# usbcan_20190426.net
KiCad netlist of a schematic drawn in EAGLE
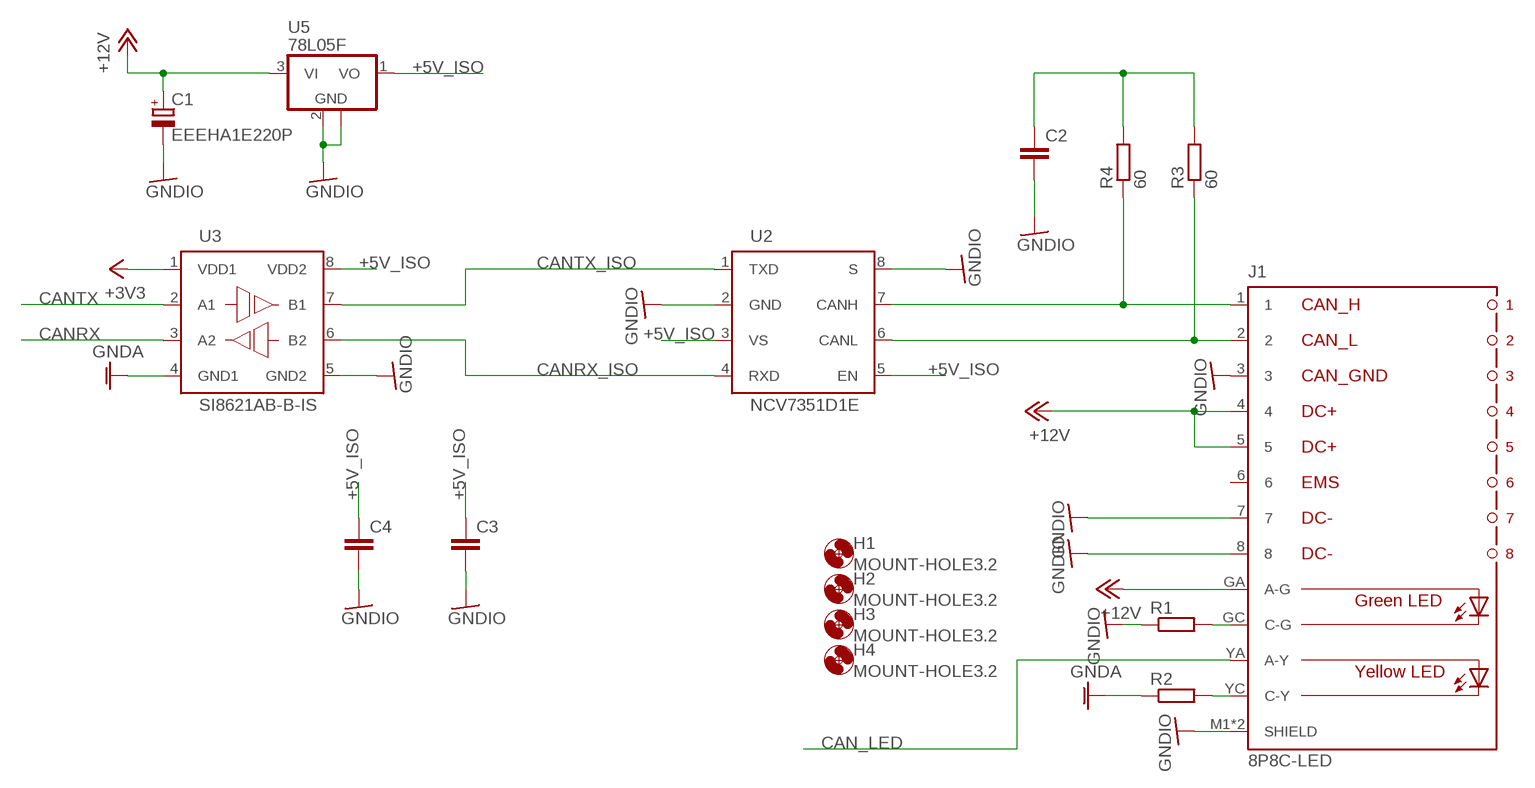
[diagram p0: schematic, sheet 1]
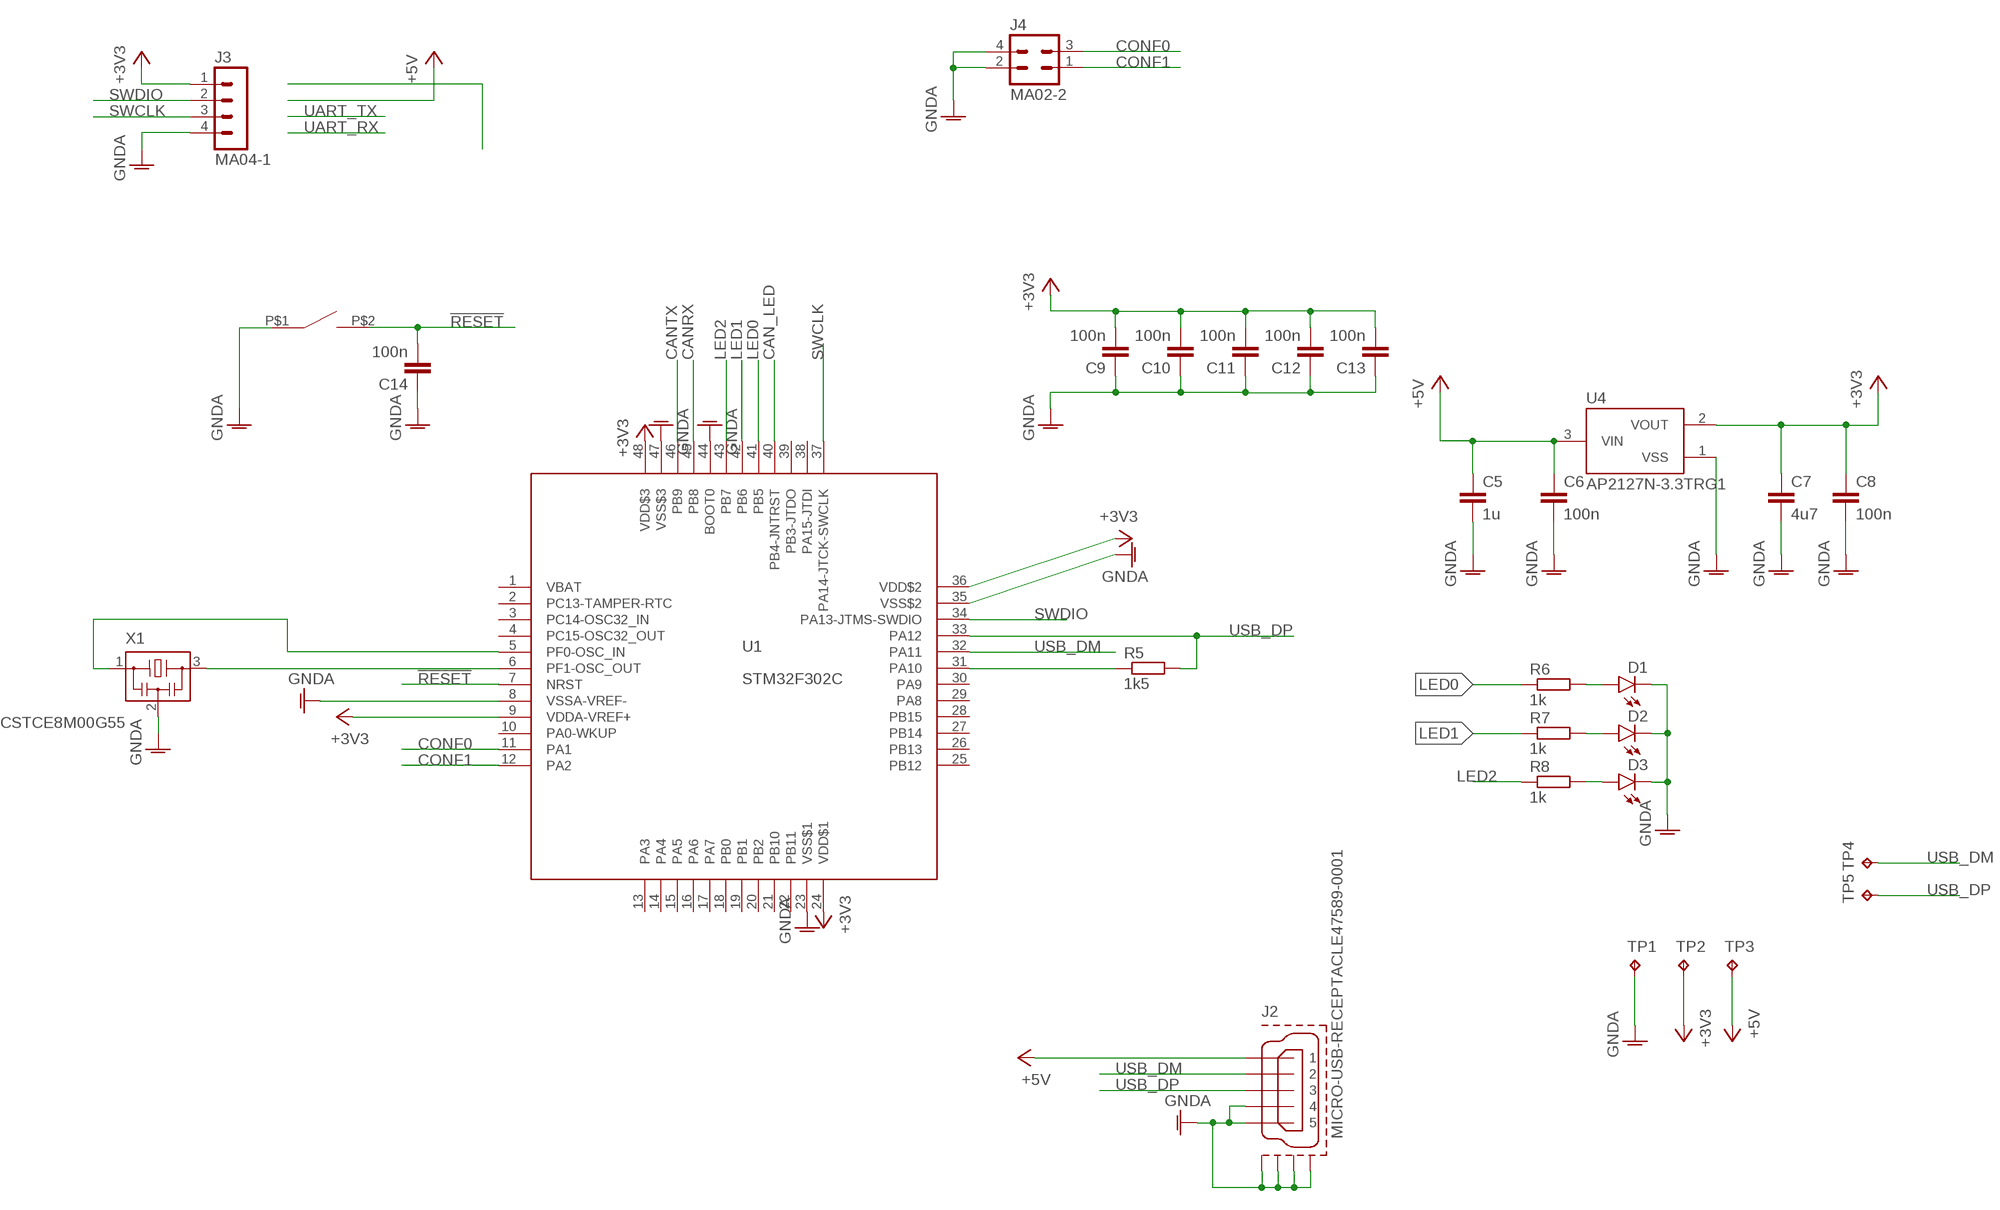
[diagram p1: schematic, sheet 2]

(export (version "E")
  (design (tool "Eeschema 10.0.6"))
  (components
    (comp (ref "C5")
      (value "1u")
      (footprint "eagle-import:C0603")
      (libsource (lib "eagle-import") (part "C-EUC0603"))
    )
    (comp (ref "C6")
      (value "100n")
      (footprint "eagle-import:C0603")
      (libsource (lib "eagle-import") (part "C-EUC0603"))
    )
    (comp (ref "C7")
      (value "4u7")
      (footprint "eagle-import:C0805")
      (libsource (lib "eagle-import") (part "C-EUC0805"))
    )
    (comp (ref "C8")
      (value "100n")
      (footprint "eagle-import:C0603")
      (libsource (lib "eagle-import") (part "C-EUC0603"))
    )
    (comp (ref "C9")
      (value "100n")
      (footprint "eagle-import:C0603")
      (libsource (lib "eagle-import") (part "C-EUC0603"))
    )
    (comp (ref "C10")
      (value "100n")
      (footprint "eagle-import:C0603")
      (libsource (lib "eagle-import") (part "C-EUC0603"))
    )
    (comp (ref "C11")
      (value "100n")
      (footprint "eagle-import:C0603")
      (libsource (lib "eagle-import") (part "C-EUC0603"))
    )
    (comp (ref "C12")
      (value "100n")
      (footprint "eagle-import:C0603")
      (libsource (lib "eagle-import") (part "C-EUC0603"))
    )
    (comp (ref "C13")
      (value "100n")
      (footprint "eagle-import:C0603")
      (libsource (lib "eagle-import") (part "C-EUC0603"))
    )
    (comp (ref "C14")
      (value "100n")
      (footprint "eagle-import:C0603")
      (libsource (lib "eagle-import") (part "C-EUC0603"))
    )
    (comp (ref "D1")
      (value "LEDCHIPLED_0805")
      (footprint "eagle-import:CHIPLED_0805")
      (libsource (lib "eagle-import") (part "LEDCHIPLED_0805"))
    )
    (comp (ref "D2")
      (value "LEDCHIPLED_0805")
      (footprint "eagle-import:CHIPLED_0805")
      (libsource (lib "eagle-import") (part "LEDCHIPLED_0805"))
    )
    (comp (ref "D3")
      (value "LEDCHIPLED_0805")
      (footprint "eagle-import:CHIPLED_0805")
      (libsource (lib "eagle-import") (part "LEDCHIPLED_0805"))
    )
    (comp (ref "J2")
      (value "MICRO-USB-RECEPTACLE47589-0001")
      (footprint "eagle-import:47589-0001")
      (libsource (lib "eagle-import") (part "MICRO-USB-RECEPTACLE47589-0001"))
    )
    (comp (ref "J3")
      (value "MA04-1")
      (footprint "eagle-import:MA04-1")
      (libsource (lib "eagle-import") (part "MA04-1"))
    )
    (comp (ref "J4")
      (value "MA02-2")
      (footprint "eagle-import:MA02-2W")
      (libsource (lib "eagle-import") (part "MA02-2"))
    )
    (comp (ref "R5")
      (value "1k5")
      (footprint "eagle-import:R0603")
      (libsource (lib "eagle-import") (part "R-EU_R0603"))
    )
    (comp (ref "R6")
      (value "1k")
      (footprint "eagle-import:R0603")
      (libsource (lib "eagle-import") (part "R-EU_R0603"))
    )
    (comp (ref "R7")
      (value "1k")
      (footprint "eagle-import:R0603")
      (libsource (lib "eagle-import") (part "R-EU_R0603"))
    )
    (comp (ref "R8")
      (value "1k")
      (footprint "eagle-import:R0603")
      (libsource (lib "eagle-import") (part "R-EU_R0603"))
    )
    (comp (ref "S1")
      (value "SWITCH_TACTILETOP")
      (footprint "eagle-import:SWITCH_TACTILE_3X6")
      (libsource (lib "eagle-import") (part "SWITCH_TACTILETOP"))
    )
    (comp (ref "TP1")
      (value "TPB1,27")
      (footprint "eagle-import:B1,27")
      (libsource (lib "eagle-import") (part "TPB1,27"))
    )
    (comp (ref "TP2")
      (value "TPB1,27")
      (footprint "eagle-import:B1,27")
      (libsource (lib "eagle-import") (part "TPB1,27"))
    )
    (comp (ref "TP3")
      (value "TPB1,27")
      (footprint "eagle-import:B1,27")
      (libsource (lib "eagle-import") (part "TPB1,27"))
    )
    (comp (ref "TP4")
      (value "TPB1,27")
      (footprint "eagle-import:B1,27")
      (libsource (lib "eagle-import") (part "TPB1,27"))
    )
    (comp (ref "TP5")
      (value "TPB1,27")
      (footprint "eagle-import:B1,27")
      (libsource (lib "eagle-import") (part "TPB1,27"))
    )
    (comp (ref "U1")
      (value "STM32F302C")
      (footprint "eagle-import:LQFP48")
      (libsource (lib "eagle-import") (part "STM32F303C"))
    )
    (comp (ref "U4")
      (value "AP2127N-3.3TRG1")
      (footprint "eagle-import:SOT95P240X110-3")
      (libsource (lib "eagle-import") (part "XC6206"))
    )
    (comp (ref "X1")
      (value "CSTCE8M00G55")
      (footprint "eagle-import:CSTCE8M00G55")
      (libsource (lib "eagle-import") (part "CSTCE8M00G55"))
    )
    (comp (ref "C1")
      (value "EEEHA1E220P")
      (footprint "eagle-import:153CLV-0605")
      (libsource (lib "eagle-import") (part "CPOL-EU153CLV-0605"))
    )
    (comp (ref "C2")
      (value "C-EUC0603")
      (footprint "eagle-import:C0603")
      (libsource (lib "eagle-import") (part "rcl_334_C-EUC0603"))
    )
    (comp (ref "C3")
      (value "C-EUC0603")
      (footprint "eagle-import:C0603")
      (libsource (lib "eagle-import") (part "rcl_334_C-EUC0603"))
    )
    (comp (ref "C4")
      (value "C-EUC0603")
      (footprint "eagle-import:C0603")
      (libsource (lib "eagle-import") (part "rcl_334_C-EUC0603"))
    )
    (comp (ref "H1")
      (value "MOUNT-HOLE3.2")
      (footprint "eagle-import:3,2")
      (libsource (lib "eagle-import") (part "MOUNT-HOLE3.2"))
    )
    (comp (ref "H2")
      (value "MOUNT-HOLE3.2")
      (footprint "eagle-import:3,2")
      (libsource (lib "eagle-import") (part "MOUNT-HOLE3.2"))
    )
    (comp (ref "H3")
      (value "MOUNT-HOLE3.2")
      (footprint "eagle-import:3,2")
      (libsource (lib "eagle-import") (part "MOUNT-HOLE3.2"))
    )
    (comp (ref "H4")
      (value "MOUNT-HOLE3.2")
      (footprint "eagle-import:3,2")
      (libsource (lib "eagle-import") (part "MOUNT-HOLE3.2"))
    )
    (comp (ref "J1")
      (value "8P8C-LED")
      (footprint "eagle-import:8P8C-LED")
      (libsource (lib "eagle-import") (part "8P8C-LED"))
    )
    (comp (ref "R1")
      (value "R-EU_R0603")
      (footprint "eagle-import:R0603")
      (libsource (lib "eagle-import") (part "rcl_334_R-EU_R0603"))
    )
    (comp (ref "R2")
      (value "R-EU_R0603")
      (footprint "eagle-import:R0603")
      (libsource (lib "eagle-import") (part "rcl_334_R-EU_R0603"))
    )
    (comp (ref "R3")
      (value "60")
      (footprint "eagle-import:R0603")
      (libsource (lib "eagle-import") (part "rcl_334_R-EU_R0603"))
    )
    (comp (ref "R4")
      (value "60")
      (footprint "eagle-import:R0603")
      (libsource (lib "eagle-import") (part "rcl_334_R-EU_R0603"))
    )
    (comp (ref "U2")
      (value "NCV7351D1E")
      (footprint "eagle-import:SO08")
      (libsource (lib "eagle-import") (part "NCV7351D1E"))
    )
    (comp (ref "U3")
      (value "SI8621AB-B-IS")
      (footprint "eagle-import:SO08")
      (libsource (lib "eagle-import") (part "SI8621AB-B-IS"))
    )
    (comp (ref "U5")
      (value "78L05F")
      (footprint "eagle-import:SOT89")
      (libsource (lib "eagle-import") (part "78LF05"))
    )
  )
  (nets
    (net (code "1") (name "+3V3") (class "Default")
      (node (ref "C10") (pin "2") (pinfunction "2_2") (pintype "passive"))
      (node (ref "C11") (pin "2") (pinfunction "2_2") (pintype "passive"))
      (node (ref "C12") (pin "2") (pinfunction "2_2") (pintype "passive"))
      (node (ref "C13") (pin "2") (pinfunction "2_2") (pintype "passive"))
      (node (ref "C7") (pin "1") (pinfunction "1_1") (pintype "passive"))
      (node (ref "C8") (pin "1") (pinfunction "1_1") (pintype "passive"))
      (node (ref "C9") (pin "2") (pinfunction "2_2") (pintype "passive"))
      (node (ref "J3") (pin "1") (pinfunction "1_1") (pintype "passive"))
      (node (ref "TP2") (pin "TP") (pinfunction "TP_TP") (pintype "input"))
      (node (ref "U1") (pin "24") (pinfunction "VDD$1_24") (pintype "passive"))
      (node (ref "U1") (pin "36") (pinfunction "VDD$2_36") (pintype "passive"))
      (node (ref "U1") (pin "48") (pinfunction "VDD$3_48") (pintype "passive"))
      (node (ref "U1") (pin "9") (pinfunction "VDDA-VREF+_9") (pintype "bidirectional"))
      (node (ref "U3") (pin "1") (pinfunction "VDD1_1") (pintype "power_in"))
      (node (ref "U4") (pin "2") (pinfunction "VOUT_2") (pintype "bidirectional"))
    )
    (net (code "2") (name "+5V") (class "Default")
      (node (ref "C5") (pin "1") (pinfunction "1_1") (pintype "passive"))
      (node (ref "C6") (pin "1") (pinfunction "1_1") (pintype "passive"))
      (node (ref "J2") (pin "1") (pinfunction "1_1") (pintype "input"))
      (node (ref "TP3") (pin "TP") (pinfunction "TP_TP") (pintype "input"))
      (node (ref "U4") (pin "3") (pinfunction "VIN_3") (pintype "bidirectional"))
    )
    (net (code "3") (name "+5V_ISO") (class "Default")
      (node (ref "C3") (pin "1") (pinfunction "1_1") (pintype "passive"))
      (node (ref "C4") (pin "1") (pinfunction "1_1") (pintype "passive"))
      (node (ref "U2") (pin "3") (pinfunction "VS_3") (pintype "power_in"))
      (node (ref "U2") (pin "5") (pinfunction "EN_5") (pintype "input"))
      (node (ref "U3") (pin "8") (pinfunction "VDD2_8") (pintype "power_in"))
      (node (ref "U5") (pin "1") (pinfunction "VO_1") (pintype "passive"))
    )
    (net (code "4") (name "+12V") (class "Default")
      (node (ref "C1") (pin "+") (pinfunction "+_+") (pintype "passive"))
      (node (ref "J1") (pin "4") (pinfunction "4_4") (pintype "input"))
      (node (ref "J1") (pin "5") (pinfunction "5_5") (pintype "input"))
      (node (ref "J1") (pin "GA") (pinfunction "A-G_GA") (pintype "passive"))
      (node (ref "U5") (pin "3") (pinfunction "VI_3") (pintype "input"))
    )
    (net (code "5") (name "CANRX") (class "Default")
      (node (ref "U1") (pin "45") (pinfunction "PB8_45") (pintype "bidirectional"))
      (node (ref "U3") (pin "3") (pinfunction "A2_3") (pintype "output"))
    )
    (net (code "6") (name "CANRX_ISO") (class "Default")
      (node (ref "U2") (pin "4") (pinfunction "RXD_4") (pintype "output"))
      (node (ref "U3") (pin "6") (pinfunction "B2_6") (pintype "output"))
    )
    (net (code "7") (name "CANTX") (class "Default")
      (node (ref "U1") (pin "46") (pinfunction "PB9_46") (pintype "bidirectional"))
      (node (ref "U3") (pin "2") (pinfunction "A1_2") (pintype "input"))
    )
    (net (code "8") (name "CANTX_ISO") (class "Default")
      (node (ref "U2") (pin "1") (pinfunction "TXD_1") (pintype "input"))
      (node (ref "U3") (pin "7") (pinfunction "B1_7") (pintype "output"))
    )
    (net (code "9") (name "CAN_LED") (class "Default")
      (node (ref "J1") (pin "YA") (pinfunction "A-Y_YA") (pintype "passive"))
      (node (ref "U1") (pin "40") (pinfunction "PB4-JNTRST_40") (pintype "bidirectional"))
    )
    (net (code "10") (name "CONF0") (class "Default")
      (node (ref "J4") (pin "3") (pinfunction "3_3") (pintype "passive"))
      (node (ref "U1") (pin "11") (pinfunction "PA1_11") (pintype "bidirectional"))
    )
    (net (code "11") (name "CONF1") (class "Default")
      (node (ref "J4") (pin "1") (pinfunction "1_1") (pintype "passive"))
      (node (ref "U1") (pin "12") (pinfunction "PA2_12") (pintype "bidirectional"))
    )
    (net (code "12") (name "GNDA") (class "Default")
      (node (ref "C10") (pin "1") (pinfunction "1_1") (pintype "passive"))
      (node (ref "C11") (pin "1") (pinfunction "1_1") (pintype "passive"))
      (node (ref "C12") (pin "1") (pinfunction "1_1") (pintype "passive"))
      (node (ref "C13") (pin "1") (pinfunction "1_1") (pintype "passive"))
      (node (ref "C14") (pin "1") (pinfunction "1_1") (pintype "passive"))
      (node (ref "C5") (pin "2") (pinfunction "2_2") (pintype "passive"))
      (node (ref "C6") (pin "2") (pinfunction "2_2") (pintype "passive"))
      (node (ref "C7") (pin "2") (pinfunction "2_2") (pintype "passive"))
      (node (ref "C8") (pin "2") (pinfunction "2_2") (pintype "passive"))
      (node (ref "C9") (pin "1") (pinfunction "1_1") (pintype "passive"))
      (node (ref "D1") (pin "C") (pinfunction "C_C") (pintype "passive"))
      (node (ref "D2") (pin "C") (pinfunction "C_C") (pintype "passive"))
      (node (ref "D3") (pin "C") (pinfunction "C_C") (pintype "passive"))
      (node (ref "J2") (pin "4") (pinfunction "4_4") (pintype "input"))
      (node (ref "J2") (pin "5") (pinfunction "5_5") (pintype "input"))
      (node (ref "J2") (pin "CASING1") (pinfunction "GND1_CASING1") (pintype "bidirectional"))
      (node (ref "J2") (pin "CASING2") (pinfunction "GND2_CASING2") (pintype "bidirectional"))
      (node (ref "J2") (pin "CASING3") (pinfunction "GND3_CASING3") (pintype "bidirectional"))
      (node (ref "J2") (pin "CASING4") (pinfunction "GND4_CASING4") (pintype "bidirectional"))
      (node (ref "J2") (pin "P$1") (pinfunction "GND1_P$1") (pintype "bidirectional"))
      (node (ref "J2") (pin "P$2") (pinfunction "GND1_P$2") (pintype "bidirectional"))
      (node (ref "J2") (pin "P$3") (pinfunction "GND2_P$3") (pintype "bidirectional"))
      (node (ref "J2") (pin "P$4") (pinfunction "GND2_P$4") (pintype "bidirectional"))
      (node (ref "J3") (pin "4") (pinfunction "4_4") (pintype "passive"))
      (node (ref "J4") (pin "2") (pinfunction "2_2") (pintype "passive"))
      (node (ref "J4") (pin "4") (pinfunction "4_4") (pintype "passive"))
      (node (ref "R2") (pin "1") (pinfunction "1_1") (pintype "passive"))
      (node (ref "S1") (pin "P$1") (pinfunction "1_P$1") (pintype "bidirectional"))
      (node (ref "TP1") (pin "TP") (pinfunction "TP_TP") (pintype "input"))
      (node (ref "U1") (pin "23") (pinfunction "VSS$1_23") (pintype "passive"))
      (node (ref "U1") (pin "35") (pinfunction "VSS$2_35") (pintype "passive"))
      (node (ref "U1") (pin "44") (pinfunction "BOOT0_44") (pintype "input"))
      (node (ref "U1") (pin "47") (pinfunction "VSS$3_47") (pintype "passive"))
      (node (ref "U1") (pin "8") (pinfunction "VSSA-VREF-_8") (pintype "bidirectional"))
      (node (ref "U3") (pin "4") (pinfunction "GND1_4") (pintype "power_in"))
      (node (ref "U4") (pin "1") (pinfunction "VSS_1") (pintype "bidirectional"))
      (node (ref "X1") (pin "2") (pinfunction "2_2") (pintype "passive"))
    )
    (net (code "13") (name "GNDIO") (class "Default")
      (node (ref "C1") (pin "-") (pinfunction "-_-") (pintype "passive"))
      (node (ref "C2") (pin "2") (pinfunction "2_2") (pintype "passive"))
      (node (ref "C3") (pin "2") (pinfunction "2_2") (pintype "passive"))
      (node (ref "C4") (pin "2") (pinfunction "2_2") (pintype "passive"))
      (node (ref "J1") (pin "3") (pinfunction "3_3") (pintype "input"))
      (node (ref "J1") (pin "7") (pinfunction "7_7") (pintype "input"))
      (node (ref "J1") (pin "8") (pinfunction "8_8") (pintype "input"))
      (node (ref "J1") (pin "M1") (pinfunction "SHIELD_M1") (pintype "passive"))
      (node (ref "J1") (pin "M2") (pinfunction "SHIELD_M2") (pintype "passive"))
      (node (ref "R1") (pin "1") (pinfunction "1_1") (pintype "passive"))
      (node (ref "U2") (pin "2") (pinfunction "GND_2") (pintype "power_in"))
      (node (ref "U2") (pin "8") (pinfunction "S_8") (pintype "input"))
      (node (ref "U3") (pin "5") (pinfunction "GND2_5") (pintype "power_in"))
      (node (ref "U5") (pin "2") (pinfunction "GND_2") (pintype "passive"))
      (node (ref "U5") (pin "2@1") (pinfunction "GND_2@1") (pintype "passive"))
    )
    (net (code "14") (name "LED0") (class "Default")
      (node (ref "R6") (pin "1") (pinfunction "1_1") (pintype "passive"))
      (node (ref "U1") (pin "41") (pinfunction "PB5_41") (pintype "bidirectional"))
    )
    (net (code "15") (name "LED1") (class "Default")
      (node (ref "R7") (pin "1") (pinfunction "1_1") (pintype "passive"))
      (node (ref "U1") (pin "42") (pinfunction "PB6_42") (pintype "bidirectional"))
    )
    (net (code "16") (name "LED2") (class "Default")
      (node (ref "R8") (pin "1") (pinfunction "1_1") (pintype "passive"))
      (node (ref "U1") (pin "43") (pinfunction "PB7_43") (pintype "bidirectional"))
    )
    (net (code "17") (name "Net-(C2-Pad1)") (class "Default")
      (node (ref "C2") (pin "1") (pinfunction "1_1") (pintype "passive"))
      (node (ref "R3") (pin "2") (pinfunction "2_2") (pintype "passive"))
      (node (ref "R4") (pin "2") (pinfunction "2_2") (pintype "passive"))
    )
    (net (code "18") (name "Net-(D1-PadA)") (class "Default")
      (node (ref "D1") (pin "A") (pinfunction "A_A") (pintype "passive"))
      (node (ref "R6") (pin "2") (pinfunction "2_2") (pintype "passive"))
    )
    (net (code "19") (name "Net-(D2-PadA)") (class "Default")
      (node (ref "D2") (pin "A") (pinfunction "A_A") (pintype "passive"))
      (node (ref "R7") (pin "2") (pinfunction "2_2") (pintype "passive"))
    )
    (net (code "20") (name "Net-(D3-PadA)") (class "Default")
      (node (ref "D3") (pin "A") (pinfunction "A_A") (pintype "passive"))
      (node (ref "R8") (pin "2") (pinfunction "2_2") (pintype "passive"))
    )
    (net (code "21") (name "Net-(J1-C-G)") (class "Default")
      (node (ref "J1") (pin "GC") (pinfunction "C-G_GC") (pintype "passive"))
      (node (ref "R1") (pin "2") (pinfunction "2_2") (pintype "passive"))
    )
    (net (code "22") (name "Net-(J1-C-Y)") (class "Default")
      (node (ref "J1") (pin "YC") (pinfunction "C-Y_YC") (pintype "passive"))
      (node (ref "R2") (pin "2") (pinfunction "2_2") (pintype "passive"))
    )
    (net (code "23") (name "Net-(U1-PA10)") (class "Default")
      (node (ref "R5") (pin "1") (pinfunction "1_1") (pintype "passive"))
      (node (ref "U1") (pin "31") (pinfunction "PA10_31") (pintype "bidirectional"))
    )
    (net (code "24") (name "Net-(U1-PF0-OSC_IN)") (class "Default")
      (node (ref "U1") (pin "5") (pinfunction "PF0-OSC_IN_5") (pintype "input"))
      (node (ref "X1") (pin "1") (pinfunction "1_1") (pintype "passive"))
    )
    (net (code "25") (name "Net-(U1-PF1-OSC_OUT)") (class "Default")
      (node (ref "U1") (pin "6") (pinfunction "PF1-OSC_OUT_6") (pintype "output"))
      (node (ref "X1") (pin "3") (pinfunction "3_3") (pintype "passive"))
    )
    (net (code "26") (name "Net-(U2-CANH)") (class "Default")
      (node (ref "J1") (pin "1") (pinfunction "1_1") (pintype "input"))
      (node (ref "R4") (pin "1") (pinfunction "1_1") (pintype "passive"))
      (node (ref "U2") (pin "7") (pinfunction "CANH_7") (pintype "output"))
    )
    (net (code "27") (name "Net-(U2-CANL)") (class "Default")
      (node (ref "J1") (pin "2") (pinfunction "2_2") (pintype "input"))
      (node (ref "R3") (pin "1") (pinfunction "1_1") (pintype "passive"))
      (node (ref "U2") (pin "6") (pinfunction "CANL_6") (pintype "output"))
    )
    (net (code "28") (name "SWCLK") (class "Default")
      (node (ref "J3") (pin "3") (pinfunction "3_3") (pintype "passive"))
      (node (ref "U1") (pin "37") (pinfunction "PA14-JTCK-SWCLK_37") (pintype "bidirectional"))
    )
    (net (code "29") (name "SWDIO") (class "Default")
      (node (ref "J3") (pin "2") (pinfunction "2_2") (pintype "passive"))
      (node (ref "U1") (pin "34") (pinfunction "PA13-JTMS-SWDIO_34") (pintype "bidirectional"))
    )
    (net (code "32") (name "USB_DM") (class "Default")
      (node (ref "J2") (pin "2") (pinfunction "2_2") (pintype "input"))
      (node (ref "TP4") (pin "TP") (pinfunction "TP_TP") (pintype "input"))
      (node (ref "U1") (pin "32") (pinfunction "PA11_32") (pintype "bidirectional"))
    )
    (net (code "33") (name "USB_DP") (class "Default")
      (node (ref "J2") (pin "3") (pinfunction "3_3") (pintype "input"))
      (node (ref "R5") (pin "2") (pinfunction "2_2") (pintype "passive"))
      (node (ref "TP5") (pin "TP") (pinfunction "TP_TP") (pintype "input"))
      (node (ref "U1") (pin "33") (pinfunction "PA12_33") (pintype "bidirectional"))
    )
    (net (code "34") (name "unconnected-(J1-Pad6)") (class "Default")
      (node (ref "J1") (pin "6") (pinfunction "6_6") (pintype "input"))
    )
    (net (code "35") (name "unconnected-(U1-PA0-WKUP-Pad10)") (class "Default")
      (node (ref "U1") (pin "10") (pinfunction "PA0-WKUP_10") (pintype "bidirectional"))
    )
    (net (code "36") (name "unconnected-(U1-PA3-Pad13)") (class "Default")
      (node (ref "U1") (pin "13") (pinfunction "PA3_13") (pintype "bidirectional"))
    )
    (net (code "37") (name "unconnected-(U1-PA4-Pad14)") (class "Default")
      (node (ref "U1") (pin "14") (pinfunction "PA4_14") (pintype "bidirectional"))
    )
    (net (code "38") (name "unconnected-(U1-PA5-Pad15)") (class "Default")
      (node (ref "U1") (pin "15") (pinfunction "PA5_15") (pintype "bidirectional"))
    )
    (net (code "39") (name "unconnected-(U1-PA6-Pad16)") (class "Default")
      (node (ref "U1") (pin "16") (pinfunction "PA6_16") (pintype "bidirectional"))
    )
    (net (code "40") (name "unconnected-(U1-PA7-Pad17)") (class "Default")
      (node (ref "U1") (pin "17") (pinfunction "PA7_17") (pintype "bidirectional"))
    )
    (net (code "41") (name "unconnected-(U1-PA8-Pad29)") (class "Default")
      (node (ref "U1") (pin "29") (pinfunction "PA8_29") (pintype "bidirectional"))
    )
    (net (code "42") (name "unconnected-(U1-PA9-Pad30)") (class "Default")
      (node (ref "U1") (pin "30") (pinfunction "PA9_30") (pintype "bidirectional"))
    )
    (net (code "43") (name "unconnected-(U1-PA15-JTDI-Pad38)") (class "Default")
      (node (ref "U1") (pin "38") (pinfunction "PA15-JTDI_38") (pintype "bidirectional"))
    )
    (net (code "44") (name "unconnected-(U1-PB0-Pad18)") (class "Default")
      (node (ref "U1") (pin "18") (pinfunction "PB0_18") (pintype "bidirectional"))
    )
    (net (code "45") (name "unconnected-(U1-PB1-Pad19)") (class "Default")
      (node (ref "U1") (pin "19") (pinfunction "PB1_19") (pintype "bidirectional"))
    )
    (net (code "46") (name "unconnected-(U1-PB2-Pad20)") (class "Default")
      (node (ref "U1") (pin "20") (pinfunction "PB2_20") (pintype "bidirectional"))
    )
    (net (code "47") (name "unconnected-(U1-PB3-JTDO-Pad39)") (class "Default")
      (node (ref "U1") (pin "39") (pinfunction "PB3-JTDO_39") (pintype "bidirectional"))
    )
    (net (code "48") (name "unconnected-(U1-PB10-Pad21)") (class "Default")
      (node (ref "U1") (pin "21") (pinfunction "PB10_21") (pintype "bidirectional"))
    )
    (net (code "49") (name "unconnected-(U1-PB11-Pad22)") (class "Default")
      (node (ref "U1") (pin "22") (pinfunction "PB11_22") (pintype "bidirectional"))
    )
    (net (code "50") (name "unconnected-(U1-PB12-Pad25)") (class "Default")
      (node (ref "U1") (pin "25") (pinfunction "PB12_25") (pintype "bidirectional"))
    )
    (net (code "51") (name "unconnected-(U1-PB13-Pad26)") (class "Default")
      (node (ref "U1") (pin "26") (pinfunction "PB13_26") (pintype "bidirectional"))
    )
    (net (code "52") (name "unconnected-(U1-PB14-Pad27)") (class "Default")
      (node (ref "U1") (pin "27") (pinfunction "PB14_27") (pintype "bidirectional"))
    )
    (net (code "53") (name "unconnected-(U1-PB15-Pad28)") (class "Default")
      (node (ref "U1") (pin "28") (pinfunction "PB15_28") (pintype "bidirectional"))
    )
    (net (code "54") (name "unconnected-(U1-PC13-TAMPER-RTC-Pad2)") (class "Default")
      (node (ref "U1") (pin "2") (pinfunction "PC13-TAMPER-RTC_2") (pintype "bidirectional"))
    )
    (net (code "55") (name "unconnected-(U1-PC14-OSC32_IN-Pad3)") (class "Default")
      (node (ref "U1") (pin "3") (pinfunction "PC14-OSC32_IN_3") (pintype "bidirectional"))
    )
    (net (code "56") (name "unconnected-(U1-PC15-OSC32_OUT-Pad4)") (class "Default")
      (node (ref "U1") (pin "4") (pinfunction "PC15-OSC32_OUT_4") (pintype "bidirectional"))
    )
    (net (code "57") (name "unconnected-(U1-VBAT-Pad1)") (class "Default")
      (node (ref "U1") (pin "1") (pinfunction "VBAT_1") (pintype "passive"))
    )
    (net (code "58") (name "~{RESET}") (class "Default")
      (node (ref "C14") (pin "2") (pinfunction "2_2") (pintype "passive"))
      (node (ref "S1") (pin "P$2") (pinfunction "2_P$2") (pintype "bidirectional"))
      (node (ref "U1") (pin "7") (pinfunction "NRST_7") (pintype "bidirectional"))
    )
  )
)
